# PSU_MAX1831_1V2_ALT.net
KiCad netlist of a schematic drawn in Altium Designer
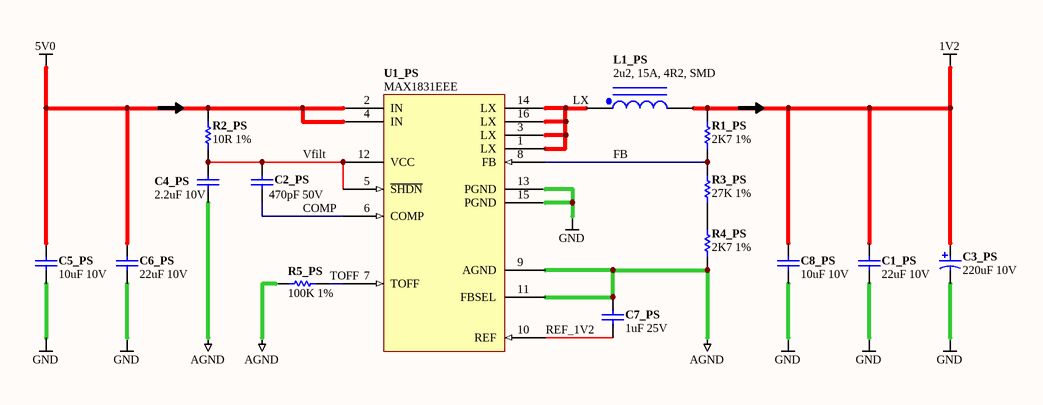
[diagram p0: PSU_MAX1831_1V2_ALT.SchDoc]

(export (version "E")
  (design (tool "Eeschema 10.0.6"))
  (components
    (comp (ref "C1_PS")
      (value "22uF 10V")
      (footprint "CAPC3225-STAR")
      (description "Capacitor, Ceramic, 22uF -20%/+80% 10V 1210 (3225) Y5V")
      (fields (field (name "TOLERANCE") "-20 / +80 %"))
      (libsource (lib "AltiumDesignLibrary") (part "CAP-NP"))
    )
    (comp (ref "C2_PS")
      (value "470pF 50V")
      (footprint "CAPC1005-STAR")
      (description "Capacitor, Ceramic, 470pF 5% 50V 0402 (1005) COG")
      (fields (field (name "TOLERANCE") "5 %"))
      (libsource (lib "AltiumDesignLibrary") (part "CAP-NP"))
    )
    (comp (ref "C3_PS")
      (value "220uF 10V")
      (footprint "CAPC7343-STAR")
      (description "Capacitor, Tantalum, 220uF 10% 10V MCCT-D (7343-31)")
      (fields (field (name "TOLERANCE") "10 %"))
      (libsource (lib "AltiumDesignLibrary") (part "CAP-P"))
    )
    (comp (ref "C4_PS")
      (value "2.2uF 10V")
      (footprint "CAPC1608-STAR")
      (description "Capacitor, Ceramic, 2.2uF 10% 10V 0603 (1608) X5R")
      (fields (field (name "TOLERANCE") "10 %"))
      (libsource (lib "AltiumDesignLibrary") (part "CAP-NP"))
    )
    (comp (ref "C5_PS")
      (value "10uF 10V")
      (footprint "CAPC2012-STAR")
      (description "Capacitor, Ceramic, 10uF 10% 10V 0805 (2012) X5R")
      (fields (field (name "TOLERANCE") "10 %"))
      (libsource (lib "AltiumDesignLibrary") (part "CAP-NP"))
    )
    (comp (ref "C6_PS")
      (value "22uF 10V")
      (footprint "CAPC3225-STAR")
      (description "Capacitor, Ceramic, 22uF -20%/+80% 10V 1210 (3225) Y5V")
      (fields (field (name "TOLERANCE") "-20 / +80 %"))
      (libsource (lib "AltiumDesignLibrary") (part "CAP-NP"))
    )
    (comp (ref "C7_PS")
      (value "1uF 25V")
      (footprint "CAPC3216-STAR")
      (description "Capacitor, Ceramic, 1uF 10% 25V 1206 (3216) X7R")
      (fields (field (name "TOLERANCE") "10 %"))
      (libsource (lib "AltiumDesignLibrary") (part "CAP-NP"))
    )
    (comp (ref "C8_PS")
      (value "10uF 10V")
      (footprint "CAPC2012-STAR")
      (description "Capacitor, Ceramic, 10uF 10% 10V 0805 (2012) X5R")
      (fields (field (name "TOLERANCE") "10 %"))
      (libsource (lib "AltiumDesignLibrary") (part "CAP-NP"))
    )
    (comp (ref "L1_PS")
      (value "2u2, 15A, 4R2, SMD")
      (footprint "IND-EPCOS-SMD-B82559")
      (description "Inductor, 2.2uH, 15A, 4R2, SMD")
      (libsource (lib "AltiumDesignLibrary") (part "IND-IRON-DOT"))
    )
    (comp (ref "R1_PS")
      (value "2K7 1%")
      (footprint "RESC1005-STAR")
      (description "Resistor, 2K7 1% 0402 (1005)")
      (fields (field (name "TOLERANCE") "1 %"))
      (libsource (lib "AltiumDesignLibrary") (part "RES"))
    )
    (comp (ref "R2_PS")
      (value "10R 1%")
      (footprint "RESC1005-STAR")
      (description "Resistor, 10R 1% 0402 (1005)")
      (fields (field (name "TOLERANCE") "1 %"))
      (libsource (lib "AltiumDesignLibrary") (part "RES"))
    )
    (comp (ref "R3_PS")
      (value "27K 1%")
      (footprint "RESC1005-STAR")
      (description "Resistor, 27K 1% 0402 (1005)")
      (fields (field (name "TOLERANCE") "1 %"))
      (libsource (lib "AltiumDesignLibrary") (part "RES"))
    )
    (comp (ref "R4_PS")
      (value "2K7 1%")
      (footprint "RESC1005-STAR")
      (description "Resistor, 2K7 1% 0402 (1005)")
      (fields (field (name "TOLERANCE") "1 %"))
      (libsource (lib "AltiumDesignLibrary") (part "RES"))
    )
    (comp (ref "R5_PS")
      (value "100K 1%")
      (footprint "RESC1005-STAR")
      (description "Resistor, 100K 1% 0402 (1005)")
      (fields (field (name "TOLERANCE") "1 %"))
      (libsource (lib "AltiumDesignLibrary") (part "RES"))
    )
    (comp (ref "U1_PS")
      (value "MAX1831EEE")
      (footprint "SOP63P602-16")
      (libsource (lib "AltiumDesignLibrary") (part "MAX1831-ALT"))
    )
  )
  (nets
    (net (code "1") (name "/COMP") (class "Default")
      (node (ref "C2_PS") (pin "2") (pinfunction "2_2") (pintype "passive"))
      (node (ref "U1_PS") (pin "6") (pinfunction "COMP_6") (pintype "input"))
    )
    (net (code "2") (name "/FB") (class "Default")
      (node (ref "R1_PS") (pin "2") (pinfunction "2_2") (pintype "passive"))
      (node (ref "R3_PS") (pin "1") (pinfunction "1_1") (pintype "passive"))
      (node (ref "U1_PS") (pin "8") (pinfunction "FB_8") (pintype "input"))
    )
    (net (code "3") (name "/LX") (class "Default")
      (node (ref "L1_PS") (pin "1") (pinfunction "1_1") (pintype "passive"))
      (node (ref "U1_PS") (pin "1") (pinfunction "LX_1") (pintype "power_in"))
      (node (ref "U1_PS") (pin "14") (pinfunction "LX_14") (pintype "power_in"))
      (node (ref "U1_PS") (pin "16") (pinfunction "LX_16") (pintype "power_in"))
      (node (ref "U1_PS") (pin "3") (pinfunction "LX_3") (pintype "power_in"))
    )
    (net (code "4") (name "/REF_1V2") (class "Default")
      (node (ref "C7_PS") (pin "2") (pinfunction "2_2") (pintype "passive"))
      (node (ref "U1_PS") (pin "10") (pinfunction "REF_10") (pintype "input"))
    )
    (net (code "5") (name "/TOFF") (class "Default")
      (node (ref "R5_PS") (pin "1") (pinfunction "1_1") (pintype "passive"))
      (node (ref "U1_PS") (pin "7") (pinfunction "TOFF_7") (pintype "input"))
    )
    (net (code "6") (name "/Vfilt") (class "Default")
      (node (ref "C2_PS") (pin "1") (pinfunction "1_1") (pintype "passive"))
      (node (ref "C4_PS") (pin "1") (pinfunction "1_1") (pintype "passive"))
      (node (ref "R2_PS") (pin "2") (pinfunction "2_2") (pintype "passive"))
      (node (ref "U1_PS") (pin "12") (pinfunction "VCC_12") (pintype "power_in"))
      (node (ref "U1_PS") (pin "5") (pinfunction "~{SHDN}_5") (pintype "input"))
    )
    (net (code "7") (name "1V2") (class "Default")
      (node (ref "C1_PS") (pin "1") (pinfunction "1_1") (pintype "passive"))
      (node (ref "C3_PS") (pin "1") (pinfunction "1_1") (pintype "passive"))
      (node (ref "C8_PS") (pin "1") (pinfunction "1_1") (pintype "passive"))
      (node (ref "L1_PS") (pin "2") (pinfunction "2_2") (pintype "passive"))
      (node (ref "R1_PS") (pin "1") (pinfunction "1_1") (pintype "passive"))
    )
    (net (code "8") (name "5V0") (class "Default")
      (node (ref "C5_PS") (pin "1") (pinfunction "1_1") (pintype "passive"))
      (node (ref "C6_PS") (pin "1") (pinfunction "1_1") (pintype "passive"))
      (node (ref "R2_PS") (pin "1") (pinfunction "1_1") (pintype "passive"))
      (node (ref "U1_PS") (pin "2") (pinfunction "IN_2") (pintype "power_in"))
      (node (ref "U1_PS") (pin "4") (pinfunction "IN_4") (pintype "power_in"))
    )
    (net (code "9") (name "AGND") (class "Default")
      (node (ref "C4_PS") (pin "2") (pinfunction "2_2") (pintype "passive"))
      (node (ref "C7_PS") (pin "1") (pinfunction "1_1") (pintype "passive"))
      (node (ref "R4_PS") (pin "2") (pinfunction "2_2") (pintype "passive"))
      (node (ref "R5_PS") (pin "2") (pinfunction "2_2") (pintype "passive"))
      (node (ref "U1_PS") (pin "11") (pinfunction "FBSEL_11") (pintype "passive"))
      (node (ref "U1_PS") (pin "9") (pinfunction "AGND_9") (pintype "power_in"))
    )
    (net (code "10") (name "GND") (class "Default")
      (node (ref "C1_PS") (pin "2") (pinfunction "2_2") (pintype "passive"))
      (node (ref "C3_PS") (pin "2") (pinfunction "2_2") (pintype "passive"))
      (node (ref "C5_PS") (pin "2") (pinfunction "2_2") (pintype "passive"))
      (node (ref "C6_PS") (pin "2") (pinfunction "2_2") (pintype "passive"))
      (node (ref "C8_PS") (pin "2") (pinfunction "2_2") (pintype "passive"))
      (node (ref "U1_PS") (pin "13") (pinfunction "PGND_13") (pintype "power_in"))
      (node (ref "U1_PS") (pin "15") (pinfunction "PGND_15") (pintype "power_in"))
    )
    (net (code "11") (name "Net-(R3_PS-Pad2)") (class "Default")
      (node (ref "R3_PS") (pin "2") (pinfunction "2_2") (pintype "passive"))
      (node (ref "R4_PS") (pin "1") (pinfunction "1_1") (pintype "passive"))
    )
  )
)
